# tractor_2v2.net
KiCad netlist of a schematic drawn in EAGLE
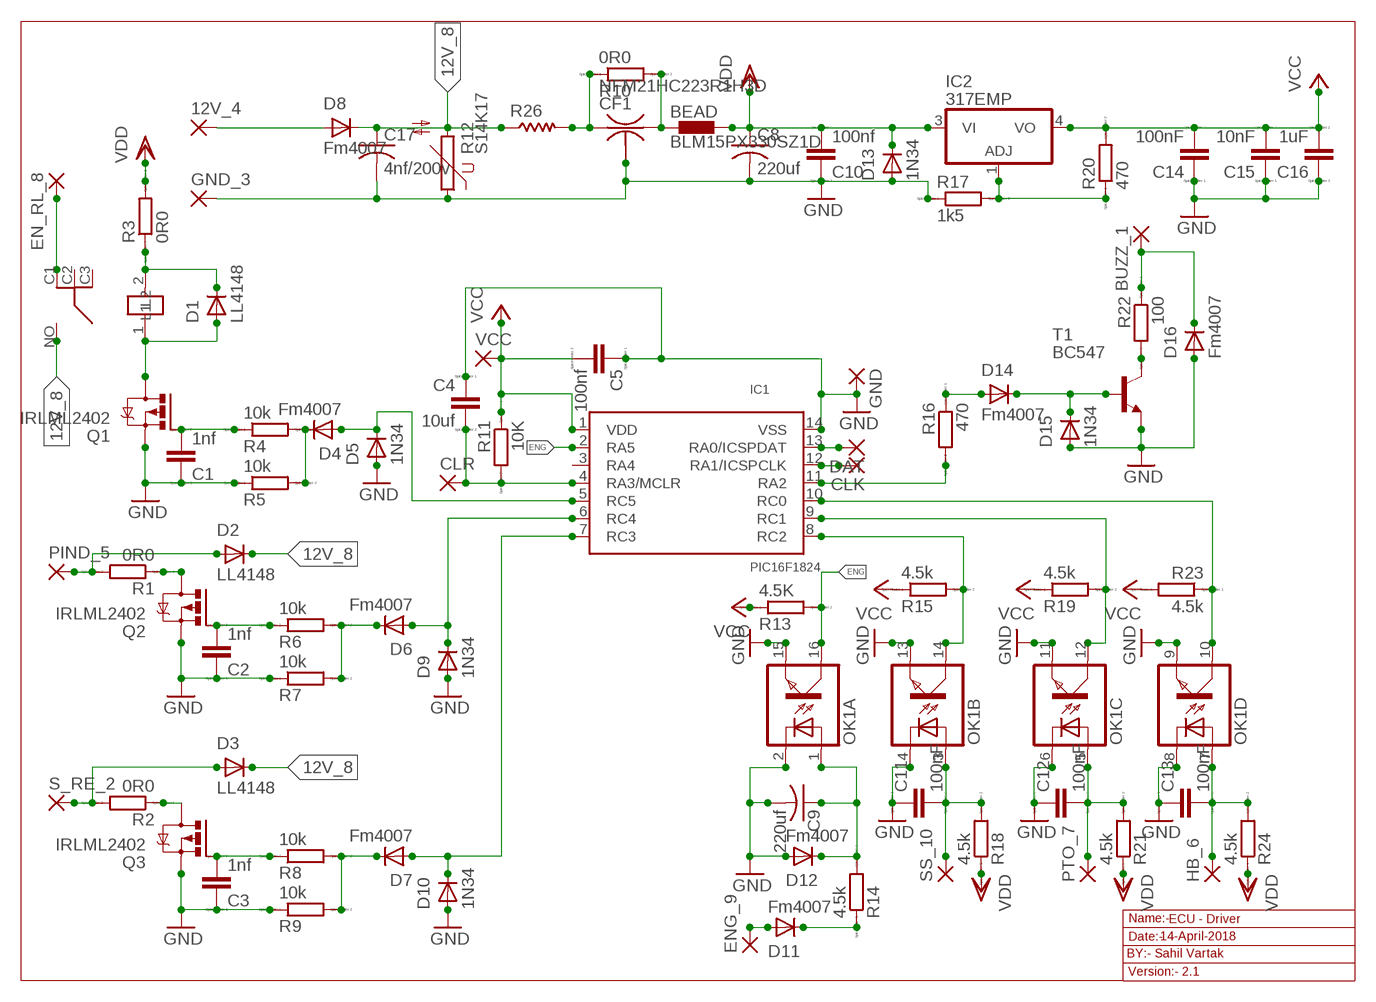
[diagram p0: schematic, sheet 1]

(export (version "E")
  (design (tool "Eeschema 10.0.6"))
  (components
    (comp (ref "12V_4")
      (value "2,54/1,1")
      (footprint "eagle-import:2,54_1,1")
      (libsource (lib "eagle-import") (part "2,54/1,1"))
    )
    (comp (ref "BEAD")
      (value "BLM15PX330SZ1D")
      (footprint "eagle-import:0402")
      (libsource (lib "eagle-import") (part "BLM15HG601SN1"))
    )
    (comp (ref "BUZZ_1")
      (value "2,54/1,1")
      (footprint "eagle-import:2,54_1,1")
      (libsource (lib "eagle-import") (part "2,54/1,1"))
    )
    (comp (ref "C1")
      (value "1nf")
      (footprint "eagle-import:C0603")
      (libsource (lib "eagle-import") (part "CC0603"))
    )
    (comp (ref "C2")
      (value "1nf")
      (footprint "eagle-import:C0603")
      (libsource (lib "eagle-import") (part "CC0603"))
    )
    (comp (ref "C3")
      (value "1nf")
      (footprint "eagle-import:C0603")
      (libsource (lib "eagle-import") (part "CC0603"))
    )
    (comp (ref "C4")
      (value "10uf")
      (footprint "eagle-import:C0603")
      (libsource (lib "eagle-import") (part "CC0603"))
    )
    (comp (ref "C5")
      (value "100nf")
      (footprint "eagle-import:C0603")
      (libsource (lib "eagle-import") (part "CC0603"))
    )
    (comp (ref "C8")
      (value "220uf")
      (footprint "eagle-import:C025-025X050")
      (libsource (lib "eagle-import") (part "C-US025-025X050"))
    )
    (comp (ref "C9")
      (value "220uf")
      (footprint "eagle-import:C025-025X050")
      (libsource (lib "eagle-import") (part "C-US025-025X050"))
    )
    (comp (ref "C10")
      (value "100nf")
      (footprint "eagle-import:C0603")
      (libsource (lib "eagle-import") (part "CC0603"))
    )
    (comp (ref "C11")
      (value "100nF")
      (footprint "eagle-import:C0603")
      (libsource (lib "eagle-import") (part "CC0603"))
    )
    (comp (ref "C12")
      (value "100nF")
      (footprint "eagle-import:C0603")
      (libsource (lib "eagle-import") (part "CC0603"))
    )
    (comp (ref "C13")
      (value "100nF")
      (footprint "eagle-import:C0603")
      (libsource (lib "eagle-import") (part "CC0603"))
    )
    (comp (ref "C14")
      (value "100nF")
      (footprint "eagle-import:C0603")
      (libsource (lib "eagle-import") (part "CC0603"))
    )
    (comp (ref "C15")
      (value "10nF")
      (footprint "eagle-import:C0603")
      (libsource (lib "eagle-import") (part "CC0603"))
    )
    (comp (ref "C16")
      (value "1uF")
      (footprint "eagle-import:C0603")
      (libsource (lib "eagle-import") (part "CC0603"))
    )
    (comp (ref "C17")
      (value "4nf/200v")
      (footprint "eagle-import:C050-045X075")
      (libsource (lib "eagle-import") (part "C-US050-045X075"))
    )
    (comp (ref "CF1")
      (value "NFM21HC223R1H3D")
      (footprint "eagle-import:NFM3DC")
      (fields (field (name "MF") "FARNELL") (field (name "MPN") "NFM3DCC470U1H3L"))
      (libsource (lib "eagle-import") (part "NFM3DC"))
    )
    (comp (ref "CLK")
      (value "1,6/0,8")
      (footprint "eagle-import:1,6_0,8")
      (libsource (lib "eagle-import") (part "1,6/0,8"))
    )
    (comp (ref "CLR")
      (value "1,6/0,8")
      (footprint "eagle-import:1,6_0,8")
      (libsource (lib "eagle-import") (part "1,6/0,8"))
    )
    (comp (ref "D1")
      (value "LL4148")
      (footprint "eagle-import:SMA-DO214AC")
      (libsource (lib "eagle-import") (part "GF1"))
    )
    (comp (ref "D2")
      (value "LL4148")
      (footprint "eagle-import:SMA-DO214AC")
      (libsource (lib "eagle-import") (part "GF1"))
    )
    (comp (ref "D3")
      (value "LL4148")
      (footprint "eagle-import:SMA-DO214AC")
      (libsource (lib "eagle-import") (part "GF1"))
    )
    (comp (ref "D4")
      (value "Fm4007")
      (footprint "eagle-import:SMA-DO214AC")
      (libsource (lib "eagle-import") (part "GF1"))
    )
    (comp (ref "D5")
      (value "1N34")
      (footprint "eagle-import:SMA-DO214AC")
      (libsource (lib "eagle-import") (part "GF1"))
    )
    (comp (ref "D6")
      (value "Fm4007")
      (footprint "eagle-import:SMA-DO214AC")
      (libsource (lib "eagle-import") (part "GF1"))
    )
    (comp (ref "D7")
      (value "Fm4007")
      (footprint "eagle-import:SMA-DO214AC")
      (libsource (lib "eagle-import") (part "GF1"))
    )
    (comp (ref "D8")
      (value "Fm4007")
      (footprint "eagle-import:SMA-DO214AC")
      (libsource (lib "eagle-import") (part "GF1"))
    )
    (comp (ref "D9")
      (value "1N34")
      (footprint "eagle-import:SMA-DO214AC")
      (libsource (lib "eagle-import") (part "GF1"))
    )
    (comp (ref "D10")
      (value "1N34")
      (footprint "eagle-import:SMA-DO214AC")
      (libsource (lib "eagle-import") (part "GF1"))
    )
    (comp (ref "D11")
      (value "Fm4007")
      (footprint "eagle-import:SMA-DO214AC")
      (libsource (lib "eagle-import") (part "GF1"))
    )
    (comp (ref "D12")
      (value "Fm4007")
      (footprint "eagle-import:SMA-DO214AC")
      (libsource (lib "eagle-import") (part "GF1"))
    )
    (comp (ref "D13")
      (value "1N34")
      (footprint "eagle-import:SMA-DO214AC")
      (libsource (lib "eagle-import") (part "GF1"))
    )
    (comp (ref "D14")
      (value "Fm4007")
      (footprint "eagle-import:SMA-DO214AC")
      (libsource (lib "eagle-import") (part "GF1"))
    )
    (comp (ref "D15")
      (value "1N34")
      (footprint "eagle-import:SMA-DO214AC")
      (libsource (lib "eagle-import") (part "GF1"))
    )
    (comp (ref "D16")
      (value "Fm4007")
      (footprint "eagle-import:SMA-DO214AC")
      (libsource (lib "eagle-import") (part "GF1"))
    )
    (comp (ref "DAT")
      (value "1,6/0,8")
      (footprint "eagle-import:1,6_0,8")
      (libsource (lib "eagle-import") (part "1,6/0,8"))
    )
    (comp (ref "ENG_9")
      (value "2,54/1,1")
      (footprint "eagle-import:2,54_1,1")
      (libsource (lib "eagle-import") (part "2,54/1,1"))
    )
    (comp (ref "EN_RL_8")
      (value "2,54/1,1")
      (footprint "eagle-import:2,54_1,1")
      (libsource (lib "eagle-import") (part "2,54/1,1"))
    )
    (comp (ref "GND")
      (value "1,6/0,8")
      (footprint "eagle-import:1,6_0,8")
      (libsource (lib "eagle-import") (part "1,6/0,8"))
    )
    (comp (ref "GND_3")
      (value "2,54/1,1")
      (footprint "eagle-import:2,54_1,1")
      (libsource (lib "eagle-import") (part "2,54/1,1"))
    )
    (comp (ref "HB_6")
      (value "2,54/1,1")
      (footprint "eagle-import:2,54_1,1")
      (libsource (lib "eagle-import") (part "2,54/1,1"))
    )
    (comp (ref "IC1")
      (value "PIC16F1824")
      (footprint "eagle-import:SO-14")
      (libsource (lib "eagle-import") (part "PIC16F1824"))
    )
    (comp (ref "IC2")
      (value "317EMP")
      (footprint "eagle-import:SOT223")
      (libsource (lib "eagle-import") (part "317EMP"))
    )
    (comp (ref "K1")
      (value "RL703")
      (footprint "eagle-import:RL703")
      (libsource (lib "eagle-import") (part "RL703"))
    )
    (comp (ref "OK1")
      (value "TLP283-4")
      (footprint "eagle-import:MINI-FLAT-16")
      (libsource (lib "eagle-import") (part "TLP283-4"))
    )
    (comp (ref "PIND_5")
      (value "2,54/1,1")
      (footprint "eagle-import:2,54_1,1")
      (libsource (lib "eagle-import") (part "2,54/1,1"))
    )
    (comp (ref "PTO_7")
      (value "2,54/1,1")
      (footprint "eagle-import:2,54_1,1")
      (libsource (lib "eagle-import") (part "2,54/1,1"))
    )
    (comp (ref "Q1")
      (value "IRLML2402")
      (footprint "eagle-import:MICRO3")
      (libsource (lib "eagle-import") (part "IRLML5203"))
    )
    (comp (ref "Q2")
      (value "IRLML2402")
      (footprint "eagle-import:MICRO3")
      (libsource (lib "eagle-import") (part "IRLML5203"))
    )
    (comp (ref "Q3")
      (value "IRLML2402")
      (footprint "eagle-import:MICRO3")
      (libsource (lib "eagle-import") (part "IRLML5203"))
    )
    (comp (ref "R1")
      (value "0R0")
      (footprint "eagle-import:R0603")
      (libsource (lib "eagle-import") (part "RR0603"))
    )
    (comp (ref "R2")
      (value "0R0")
      (footprint "eagle-import:R0603")
      (libsource (lib "eagle-import") (part "RR0603"))
    )
    (comp (ref "R3")
      (value "0R0")
      (footprint "eagle-import:R0603")
      (libsource (lib "eagle-import") (part "RR0603"))
    )
    (comp (ref "R4")
      (value "10k")
      (footprint "eagle-import:R0603")
      (libsource (lib "eagle-import") (part "RR0603"))
    )
    (comp (ref "R5")
      (value "10k")
      (footprint "eagle-import:R0603")
      (libsource (lib "eagle-import") (part "RR0603"))
    )
    (comp (ref "R6")
      (value "10k")
      (footprint "eagle-import:R0603")
      (libsource (lib "eagle-import") (part "RR0603"))
    )
    (comp (ref "R7")
      (value "10k")
      (footprint "eagle-import:R0603")
      (libsource (lib "eagle-import") (part "RR0603"))
    )
    (comp (ref "R8")
      (value "10k")
      (footprint "eagle-import:R0603")
      (libsource (lib "eagle-import") (part "RR0603"))
    )
    (comp (ref "R9")
      (value "10k")
      (footprint "eagle-import:R0603")
      (libsource (lib "eagle-import") (part "RR0603"))
    )
    (comp (ref "R10")
      (value "0R0")
      (footprint "eagle-import:R0603")
      (libsource (lib "eagle-import") (part "RR0603"))
    )
    (comp (ref "R11")
      (value "10K")
      (footprint "eagle-import:R0603")
      (libsource (lib "eagle-import") (part "RR0603"))
    )
    (comp (ref "R12")
      (value "S14K17")
      (footprint "eagle-import:S14K17")
      (libsource (lib "eagle-import") (part "S14K17"))
    )
    (comp (ref "R13")
      (value "4.5K")
      (footprint "eagle-import:R0603")
      (libsource (lib "eagle-import") (part "RR0603"))
    )
    (comp (ref "R14")
      (value "4.5k")
      (footprint "eagle-import:R0603")
      (libsource (lib "eagle-import") (part "RR0603"))
    )
    (comp (ref "R15")
      (value "4.5k")
      (footprint "eagle-import:R0603")
      (libsource (lib "eagle-import") (part "RR0603"))
    )
    (comp (ref "R16")
      (value "470")
      (footprint "eagle-import:R0603")
      (libsource (lib "eagle-import") (part "RR0603"))
    )
    (comp (ref "R17")
      (value "1k5")
      (footprint "eagle-import:R0603")
      (libsource (lib "eagle-import") (part "RR0603"))
    )
    (comp (ref "R18")
      (value "4.5k")
      (footprint "eagle-import:R0603")
      (libsource (lib "eagle-import") (part "RR0603"))
    )
    (comp (ref "R19")
      (value "4.5k")
      (footprint "eagle-import:R0603")
      (libsource (lib "eagle-import") (part "RR0603"))
    )
    (comp (ref "R20")
      (value "470")
      (footprint "eagle-import:R0603")
      (libsource (lib "eagle-import") (part "RR0603"))
    )
    (comp (ref "R21")
      (value "4.5k")
      (footprint "eagle-import:R0603")
      (libsource (lib "eagle-import") (part "RR0603"))
    )
    (comp (ref "R22")
      (value "100")
      (footprint "eagle-import:R0603")
      (libsource (lib "eagle-import") (part "RR0603"))
    )
    (comp (ref "R23")
      (value "4.5k")
      (footprint "eagle-import:R0603")
      (libsource (lib "eagle-import") (part "RR0603"))
    )
    (comp (ref "R24")
      (value "4.5k")
      (footprint "eagle-import:R0603")
      (libsource (lib "eagle-import") (part "RR0603"))
    )
    (comp (ref "R26")
      (value "R-US_WSC2515")
      (footprint "eagle-import:WSC2515")
      (libsource (lib "eagle-import") (part "R-US_WSC2515"))
    )
    (comp (ref "SS_10")
      (value "2,54/1,1")
      (footprint "eagle-import:2,54_1,1")
      (libsource (lib "eagle-import") (part "2,54/1,1"))
    )
    (comp (ref "S_RE_2")
      (value "2,54/1,1")
      (footprint "eagle-import:2,54_1,1")
      (libsource (lib "eagle-import") (part "2,54/1,1"))
    )
    (comp (ref "T1")
      (value "BC547")
      (footprint "eagle-import:TO92")
      (libsource (lib "eagle-import") (part "BC547"))
    )
    (comp (ref "VCC")
      (value "1,6/0,8")
      (footprint "eagle-import:1,6_0,8")
      (libsource (lib "eagle-import") (part "1,6/0,8"))
    )
  )
  (nets
    (net (code "1") (name "12V_8") (class "Default")
      (node (ref "C17") (pin "1") (pinfunction "1_1") (pintype "passive"))
      (node (ref "D2") (pin "K") (pinfunction "C_K") (pintype "passive"))
      (node (ref "D3") (pin "K") (pinfunction "C_K") (pintype "passive"))
      (node (ref "D8") (pin "K") (pinfunction "C_K") (pintype "passive"))
      (node (ref "K1") (pin "NO") (pinfunction "NO_NO") (pintype "bidirectional"))
      (node (ref "R12") (pin "2") (pinfunction "2_2") (pintype "passive"))
      (node (ref "R26") (pin "1") (pinfunction "1_1") (pintype "passive"))
    )
    (net (code "2") (name "ENG") (class "Default")
      (node (ref "IC1") (pin "2") (pinfunction "RA5_2") (pintype "bidirectional"))
      (node (ref "OK1") (pin "16") (pinfunction "COL_16") (pintype "passive"))
      (node (ref "R13") (pin "2") (pinfunction "2_2") (pintype "passive"))
    )
    (net (code "3") (name "GND") (class "Default")
      (node (ref "C1") (pin "1") (pinfunction "1_1") (pintype "passive"))
      (node (ref "C10") (pin "1") (pinfunction "1_1") (pintype "passive"))
      (node (ref "C11") (pin "1") (pinfunction "1_1") (pintype "passive"))
      (node (ref "C12") (pin "1") (pinfunction "1_1") (pintype "passive"))
      (node (ref "C13") (pin "1") (pinfunction "1_1") (pintype "passive"))
      (node (ref "C14") (pin "1") (pinfunction "1_1") (pintype "passive"))
      (node (ref "C15") (pin "1") (pinfunction "1_1") (pintype "passive"))
      (node (ref "C16") (pin "1") (pinfunction "1_1") (pintype "passive"))
      (node (ref "C17") (pin "2") (pinfunction "2_2") (pintype "passive"))
      (node (ref "C2") (pin "1") (pinfunction "1_1") (pintype "passive"))
      (node (ref "C3") (pin "1") (pinfunction "1_1") (pintype "passive"))
      (node (ref "C4") (pin "1") (pinfunction "1_1") (pintype "passive"))
      (node (ref "C5") (pin "1") (pinfunction "1_1") (pintype "passive"))
      (node (ref "C8") (pin "2") (pinfunction "2_2") (pintype "passive"))
      (node (ref "C9") (pin "2") (pinfunction "2_2") (pintype "passive"))
      (node (ref "CF1") (pin "2@1") (pinfunction "2_2@1") (pintype "passive"))
      (node (ref "D10") (pin "A") (pinfunction "A_A") (pintype "passive"))
      (node (ref "D12") (pin "A") (pinfunction "A_A") (pintype "passive"))
      (node (ref "D13") (pin "A") (pinfunction "A_A") (pintype "passive"))
      (node (ref "D15") (pin "A") (pinfunction "A_A") (pintype "passive"))
      (node (ref "D16") (pin "A") (pinfunction "A_A") (pintype "passive"))
      (node (ref "D5") (pin "A") (pinfunction "A_A") (pintype "passive"))
      (node (ref "D9") (pin "A") (pinfunction "A_A") (pintype "passive"))
      (node (ref "GND") (pin "1") (pinfunction "P_1") (pintype "passive"))
      (node (ref "GND_3") (pin "1") (pinfunction "P_1") (pintype "passive"))
      (node (ref "IC1") (pin "14") (pinfunction "VSS_14") (pintype "bidirectional"))
      (node (ref "OK1") (pin "11") (pinfunction "EMIT_11") (pintype "passive"))
      (node (ref "OK1") (pin "13") (pinfunction "EMIT_13") (pintype "passive"))
      (node (ref "OK1") (pin "15") (pinfunction "EMIT_15") (pintype "passive"))
      (node (ref "OK1") (pin "2") (pinfunction "C_2") (pintype "passive"))
      (node (ref "OK1") (pin "4") (pinfunction "C_4") (pintype "passive"))
      (node (ref "OK1") (pin "6") (pinfunction "C_6") (pintype "passive"))
      (node (ref "OK1") (pin "8") (pinfunction "C_8") (pintype "passive"))
      (node (ref "OK1") (pin "9") (pinfunction "EMIT_9") (pintype "passive"))
      (node (ref "Q1") (pin "2") (pinfunction "S_2") (pintype "passive"))
      (node (ref "Q2") (pin "2") (pinfunction "S_2") (pintype "passive"))
      (node (ref "Q3") (pin "2") (pinfunction "S_2") (pintype "passive"))
      (node (ref "R12") (pin "1") (pinfunction "1_1") (pintype "passive"))
      (node (ref "R17") (pin "1") (pinfunction "1_1") (pintype "passive"))
      (node (ref "R5") (pin "1") (pinfunction "1_1") (pintype "passive"))
      (node (ref "R7") (pin "1") (pinfunction "1_1") (pintype "passive"))
      (node (ref "R9") (pin "1") (pinfunction "1_1") (pintype "passive"))
      (node (ref "T1") (pin "1") (pinfunction "E_1") (pintype "passive"))
    )
    (net (code "4") (name "Net-(12V_4-P)") (class "Default")
      (node (ref "12V_4") (pin "1") (pinfunction "P_1") (pintype "passive"))
      (node (ref "D8") (pin "A") (pinfunction "A_A") (pintype "passive"))
    )
    (net (code "5") (name "Net-(BEAD-Pad1)") (class "Default")
      (node (ref "BEAD") (pin "1") (pinfunction "1_1") (pintype "passive"))
      (node (ref "CF1") (pin "3") (pinfunction "3_3") (pintype "passive"))
      (node (ref "R10") (pin "2") (pinfunction "2_2") (pintype "passive"))
    )
    (net (code "6") (name "Net-(BUZZ_1-P)") (class "Default")
      (node (ref "BUZZ_1") (pin "1") (pinfunction "P_1") (pintype "passive"))
      (node (ref "D16") (pin "K") (pinfunction "C_K") (pintype "passive"))
      (node (ref "R22") (pin "1") (pinfunction "1_1") (pintype "passive"))
    )
    (net (code "7") (name "Net-(CF1-Pad1)") (class "Default")
      (node (ref "CF1") (pin "1") (pinfunction "1_1") (pintype "passive"))
      (node (ref "R10") (pin "1") (pinfunction "1_1") (pintype "passive"))
      (node (ref "R26") (pin "2") (pinfunction "2_2") (pintype "passive"))
    )
    (net (code "8") (name "Net-(CLK-P)") (class "Default")
      (node (ref "CLK") (pin "1") (pinfunction "P_1") (pintype "passive"))
      (node (ref "IC1") (pin "12") (pinfunction "RA1/ICSPCLK_12") (pintype "bidirectional"))
    )
    (net (code "9") (name "Net-(CLR-P)") (class "Default")
      (node (ref "C4") (pin "2") (pinfunction "2_2") (pintype "passive"))
      (node (ref "CLR") (pin "1") (pinfunction "P_1") (pintype "passive"))
      (node (ref "IC1") (pin "4") (pinfunction "RA3/MCLR_4") (pintype "bidirectional"))
      (node (ref "R11") (pin "2") (pinfunction "2_2") (pintype "passive"))
    )
    (net (code "10") (name "Net-(D1-C)") (class "Default")
      (node (ref "D1") (pin "K") (pinfunction "C_K") (pintype "passive"))
      (node (ref "K1") (pin "2") (pinfunction "L1_2") (pintype "bidirectional"))
      (node (ref "R3") (pin "1") (pinfunction "1_1") (pintype "passive"))
    )
    (net (code "11") (name "Net-(D4-C)") (class "Default")
      (node (ref "D4") (pin "K") (pinfunction "C_K") (pintype "passive"))
      (node (ref "R4") (pin "2") (pinfunction "2_2") (pintype "passive"))
      (node (ref "R5") (pin "2") (pinfunction "2_2") (pintype "passive"))
    )
    (net (code "12") (name "Net-(D5-C)") (class "Default")
      (node (ref "D4") (pin "A") (pinfunction "A_A") (pintype "passive"))
      (node (ref "D5") (pin "K") (pinfunction "C_K") (pintype "passive"))
      (node (ref "IC1") (pin "5") (pinfunction "RC5_5") (pintype "bidirectional"))
    )
    (net (code "13") (name "Net-(D6-C)") (class "Default")
      (node (ref "D6") (pin "K") (pinfunction "C_K") (pintype "passive"))
      (node (ref "R6") (pin "2") (pinfunction "2_2") (pintype "passive"))
      (node (ref "R7") (pin "2") (pinfunction "2_2") (pintype "passive"))
    )
    (net (code "14") (name "Net-(D7-C)") (class "Default")
      (node (ref "D7") (pin "K") (pinfunction "C_K") (pintype "passive"))
      (node (ref "R8") (pin "2") (pinfunction "2_2") (pintype "passive"))
      (node (ref "R9") (pin "2") (pinfunction "2_2") (pintype "passive"))
    )
    (net (code "15") (name "Net-(D9-C)") (class "Default")
      (node (ref "D6") (pin "A") (pinfunction "A_A") (pintype "passive"))
      (node (ref "D9") (pin "K") (pinfunction "C_K") (pintype "passive"))
      (node (ref "IC1") (pin "6") (pinfunction "RC4_6") (pintype "bidirectional"))
    )
    (net (code "16") (name "Net-(D10-C)") (class "Default")
      (node (ref "D10") (pin "K") (pinfunction "C_K") (pintype "passive"))
      (node (ref "D7") (pin "A") (pinfunction "A_A") (pintype "passive"))
      (node (ref "IC1") (pin "7") (pinfunction "RC3_7") (pintype "bidirectional"))
    )
    (net (code "17") (name "Net-(D11-C)") (class "Default")
      (node (ref "D11") (pin "K") (pinfunction "C_K") (pintype "passive"))
      (node (ref "R14") (pin "1") (pinfunction "1_1") (pintype "passive"))
    )
    (net (code "18") (name "Net-(D12-C)") (class "Default")
      (node (ref "C9") (pin "1") (pinfunction "1_1") (pintype "passive"))
      (node (ref "D12") (pin "K") (pinfunction "C_K") (pintype "passive"))
      (node (ref "OK1") (pin "1") (pinfunction "A_1") (pintype "passive"))
      (node (ref "R14") (pin "2") (pinfunction "2_2") (pintype "passive"))
    )
    (net (code "19") (name "Net-(D14-C)") (class "Default")
      (node (ref "D14") (pin "K") (pinfunction "C_K") (pintype "passive"))
      (node (ref "D15") (pin "K") (pinfunction "C_K") (pintype "passive"))
      (node (ref "T1") (pin "2") (pinfunction "B_2") (pintype "passive"))
    )
    (net (code "20") (name "Net-(D14-PadA)") (class "Default")
      (node (ref "D14") (pin "A") (pinfunction "A_A") (pintype "passive"))
      (node (ref "R16") (pin "1") (pinfunction "1_1") (pintype "passive"))
    )
    (net (code "21") (name "Net-(DAT-P)") (class "Default")
      (node (ref "DAT") (pin "1") (pinfunction "P_1") (pintype "passive"))
      (node (ref "IC1") (pin "13") (pinfunction "RA0/ICSPDAT_13") (pintype "bidirectional"))
    )
    (net (code "22") (name "Net-(ENG_9-P)") (class "Default")
      (node (ref "D11") (pin "A") (pinfunction "A_A") (pintype "passive"))
      (node (ref "ENG_9") (pin "1") (pinfunction "P_1") (pintype "passive"))
    )
    (net (code "23") (name "Net-(EN_RL_8-P)") (class "Default")
      (node (ref "EN_RL_8") (pin "1") (pinfunction "P_1") (pintype "passive"))
      (node (ref "K1") (pin "C1") (pinfunction "C1_C1") (pintype "bidirectional"))
    )
    (net (code "24") (name "Net-(HB_6-P)") (class "Default")
      (node (ref "C13") (pin "2") (pinfunction "2_2") (pintype "passive"))
      (node (ref "HB_6") (pin "1") (pinfunction "P_1") (pintype "passive"))
      (node (ref "OK1") (pin "7") (pinfunction "A_7") (pintype "passive"))
      (node (ref "R24") (pin "2") (pinfunction "2_2") (pintype "passive"))
    )
    (net (code "25") (name "Net-(IC1-RA2)") (class "Default")
      (node (ref "IC1") (pin "11") (pinfunction "RA2_11") (pintype "bidirectional"))
      (node (ref "R16") (pin "2") (pinfunction "2_2") (pintype "passive"))
    )
    (net (code "26") (name "Net-(IC1-RC0)") (class "Default")
      (node (ref "IC1") (pin "10") (pinfunction "RC0_10") (pintype "bidirectional"))
      (node (ref "OK1") (pin "10") (pinfunction "COL_10") (pintype "passive"))
      (node (ref "R23") (pin "1") (pinfunction "1_1") (pintype "passive"))
    )
    (net (code "27") (name "Net-(IC1-RC1)") (class "Default")
      (node (ref "IC1") (pin "9") (pinfunction "RC1_9") (pintype "bidirectional"))
      (node (ref "OK1") (pin "12") (pinfunction "COL_12") (pintype "passive"))
      (node (ref "R19") (pin "2") (pinfunction "2_2") (pintype "passive"))
    )
    (net (code "28") (name "Net-(IC1-RC2)") (class "Default")
      (node (ref "IC1") (pin "8") (pinfunction "RC2_8") (pintype "bidirectional"))
      (node (ref "OK1") (pin "14") (pinfunction "COL_14") (pintype "passive"))
      (node (ref "R15") (pin "2") (pinfunction "2_2") (pintype "passive"))
    )
    (net (code "29") (name "Net-(IC2-ADJ)") (class "Default")
      (node (ref "IC2") (pin "1") (pinfunction "ADJ_1") (pintype "input"))
      (node (ref "R17") (pin "2") (pinfunction "2_2") (pintype "passive"))
      (node (ref "R20") (pin "1") (pinfunction "1_1") (pintype "passive"))
    )
    (net (code "30") (name "Net-(K1-L2)") (class "Default")
      (node (ref "D1") (pin "A") (pinfunction "A_A") (pintype "passive"))
      (node (ref "K1") (pin "1") (pinfunction "L2_1") (pintype "bidirectional"))
      (node (ref "Q1") (pin "3") (pinfunction "D_3") (pintype "passive"))
    )
    (net (code "31") (name "Net-(OK1B-A)") (class "Default")
      (node (ref "C11") (pin "2") (pinfunction "2_2") (pintype "passive"))
      (node (ref "OK1") (pin "3") (pinfunction "A_3") (pintype "passive"))
      (node (ref "R18") (pin "2") (pinfunction "2_2") (pintype "passive"))
      (node (ref "SS_10") (pin "1") (pinfunction "P_1") (pintype "passive"))
    )
    (net (code "32") (name "Net-(OK1C-A)") (class "Default")
      (node (ref "C12") (pin "2") (pinfunction "2_2") (pintype "passive"))
      (node (ref "OK1") (pin "5") (pinfunction "A_5") (pintype "passive"))
      (node (ref "PTO_7") (pin "1") (pinfunction "P_1") (pintype "passive"))
      (node (ref "R21") (pin "2") (pinfunction "2_2") (pintype "passive"))
    )
    (net (code "33") (name "Net-(PIND_5-P)") (class "Default")
      (node (ref "D2") (pin "A") (pinfunction "A_A") (pintype "passive"))
      (node (ref "PIND_5") (pin "1") (pinfunction "P_1") (pintype "passive"))
      (node (ref "R1") (pin "2") (pinfunction "2_2") (pintype "passive"))
    )
    (net (code "34") (name "Net-(Q1-G)") (class "Default")
      (node (ref "C1") (pin "2") (pinfunction "2_2") (pintype "passive"))
      (node (ref "Q1") (pin "1") (pinfunction "G_1") (pintype "passive"))
      (node (ref "R4") (pin "1") (pinfunction "1_1") (pintype "passive"))
    )
    (net (code "35") (name "Net-(Q2-D)") (class "Default")
      (node (ref "Q2") (pin "3") (pinfunction "D_3") (pintype "passive"))
      (node (ref "R1") (pin "1") (pinfunction "1_1") (pintype "passive"))
    )
    (net (code "36") (name "Net-(Q2-G)") (class "Default")
      (node (ref "C2") (pin "2") (pinfunction "2_2") (pintype "passive"))
      (node (ref "Q2") (pin "1") (pinfunction "G_1") (pintype "passive"))
      (node (ref "R6") (pin "1") (pinfunction "1_1") (pintype "passive"))
    )
    (net (code "37") (name "Net-(Q3-D)") (class "Default")
      (node (ref "Q3") (pin "3") (pinfunction "D_3") (pintype "passive"))
      (node (ref "R2") (pin "1") (pinfunction "1_1") (pintype "passive"))
    )
    (net (code "38") (name "Net-(Q3-G)") (class "Default")
      (node (ref "C3") (pin "2") (pinfunction "2_2") (pintype "passive"))
      (node (ref "Q3") (pin "1") (pinfunction "G_1") (pintype "passive"))
      (node (ref "R8") (pin "1") (pinfunction "1_1") (pintype "passive"))
    )
    (net (code "39") (name "Net-(S_RE_2-P)") (class "Default")
      (node (ref "D3") (pin "A") (pinfunction "A_A") (pintype "passive"))
      (node (ref "R2") (pin "2") (pinfunction "2_2") (pintype "passive"))
      (node (ref "S_RE_2") (pin "1") (pinfunction "P_1") (pintype "passive"))
    )
    (net (code "40") (name "Net-(T1-C)") (class "Default")
      (node (ref "R22") (pin "2") (pinfunction "2_2") (pintype "passive"))
      (node (ref "T1") (pin "3") (pinfunction "C_3") (pintype "passive"))
    )
    (net (code "41") (name "VCC") (class "Default")
      (node (ref "C14") (pin "2") (pinfunction "2_2") (pintype "passive"))
      (node (ref "C15") (pin "2") (pinfunction "2_2") (pintype "passive"))
      (node (ref "C16") (pin "2") (pinfunction "2_2") (pintype "passive"))
      (node (ref "C5") (pin "2") (pinfunction "2_2") (pintype "passive"))
      (node (ref "IC1") (pin "1") (pinfunction "VDD_1") (pintype "bidirectional"))
      (node (ref "IC2") (pin "4") (pinfunction "VO_4") (pintype "passive"))
      (node (ref "R11") (pin "1") (pinfunction "1_1") (pintype "passive"))
      (node (ref "R13") (pin "1") (pinfunction "1_1") (pintype "passive"))
      (node (ref "R15") (pin "1") (pinfunction "1_1") (pintype "passive"))
      (node (ref "R19") (pin "1") (pinfunction "1_1") (pintype "passive"))
      (node (ref "R20") (pin "2") (pinfunction "2_2") (pintype "passive"))
      (node (ref "R23") (pin "2") (pinfunction "2_2") (pintype "passive"))
      (node (ref "VCC") (pin "1") (pinfunction "P_1") (pintype "passive"))
    )
    (net (code "42") (name "VDD") (class "Default")
      (node (ref "BEAD") (pin "2") (pinfunction "2_2") (pintype "passive"))
      (node (ref "C10") (pin "2") (pinfunction "2_2") (pintype "passive"))
      (node (ref "C8") (pin "1") (pinfunction "1_1") (pintype "passive"))
      (node (ref "D13") (pin "K") (pinfunction "C_K") (pintype "passive"))
      (node (ref "IC2") (pin "3") (pinfunction "VI_3") (pintype "input"))
      (node (ref "R18") (pin "1") (pinfunction "1_1") (pintype "passive"))
      (node (ref "R21") (pin "1") (pinfunction "1_1") (pintype "passive"))
      (node (ref "R24") (pin "1") (pinfunction "1_1") (pintype "passive"))
      (node (ref "R3") (pin "2") (pinfunction "2_2") (pintype "passive"))
    )
    (net (code "43") (name "unconnected-(CF1-2-Pad2@2)") (class "Default")
      (node (ref "CF1") (pin "2@2") (pinfunction "2_2@2") (pintype "passive"))
    )
    (net (code "44") (name "unconnected-(IC1-RA4-Pad3)") (class "Default")
      (node (ref "IC1") (pin "3") (pinfunction "RA4_3") (pintype "bidirectional"))
    )
    (net (code "45") (name "unconnected-(K1-PadC2)") (class "Default")
      (node (ref "K1") (pin "C2") (pinfunction "C2_C2") (pintype "bidirectional"))
    )
    (net (code "46") (name "unconnected-(K1-PadC3)") (class "Default")
      (node (ref "K1") (pin "C3") (pinfunction "C3_C3") (pintype "bidirectional"))
    )
  )
)
